# Grove_-_Barometer_Sensor_BMP280_v1_0.net
KiCad netlist of a schematic drawn in EAGLE
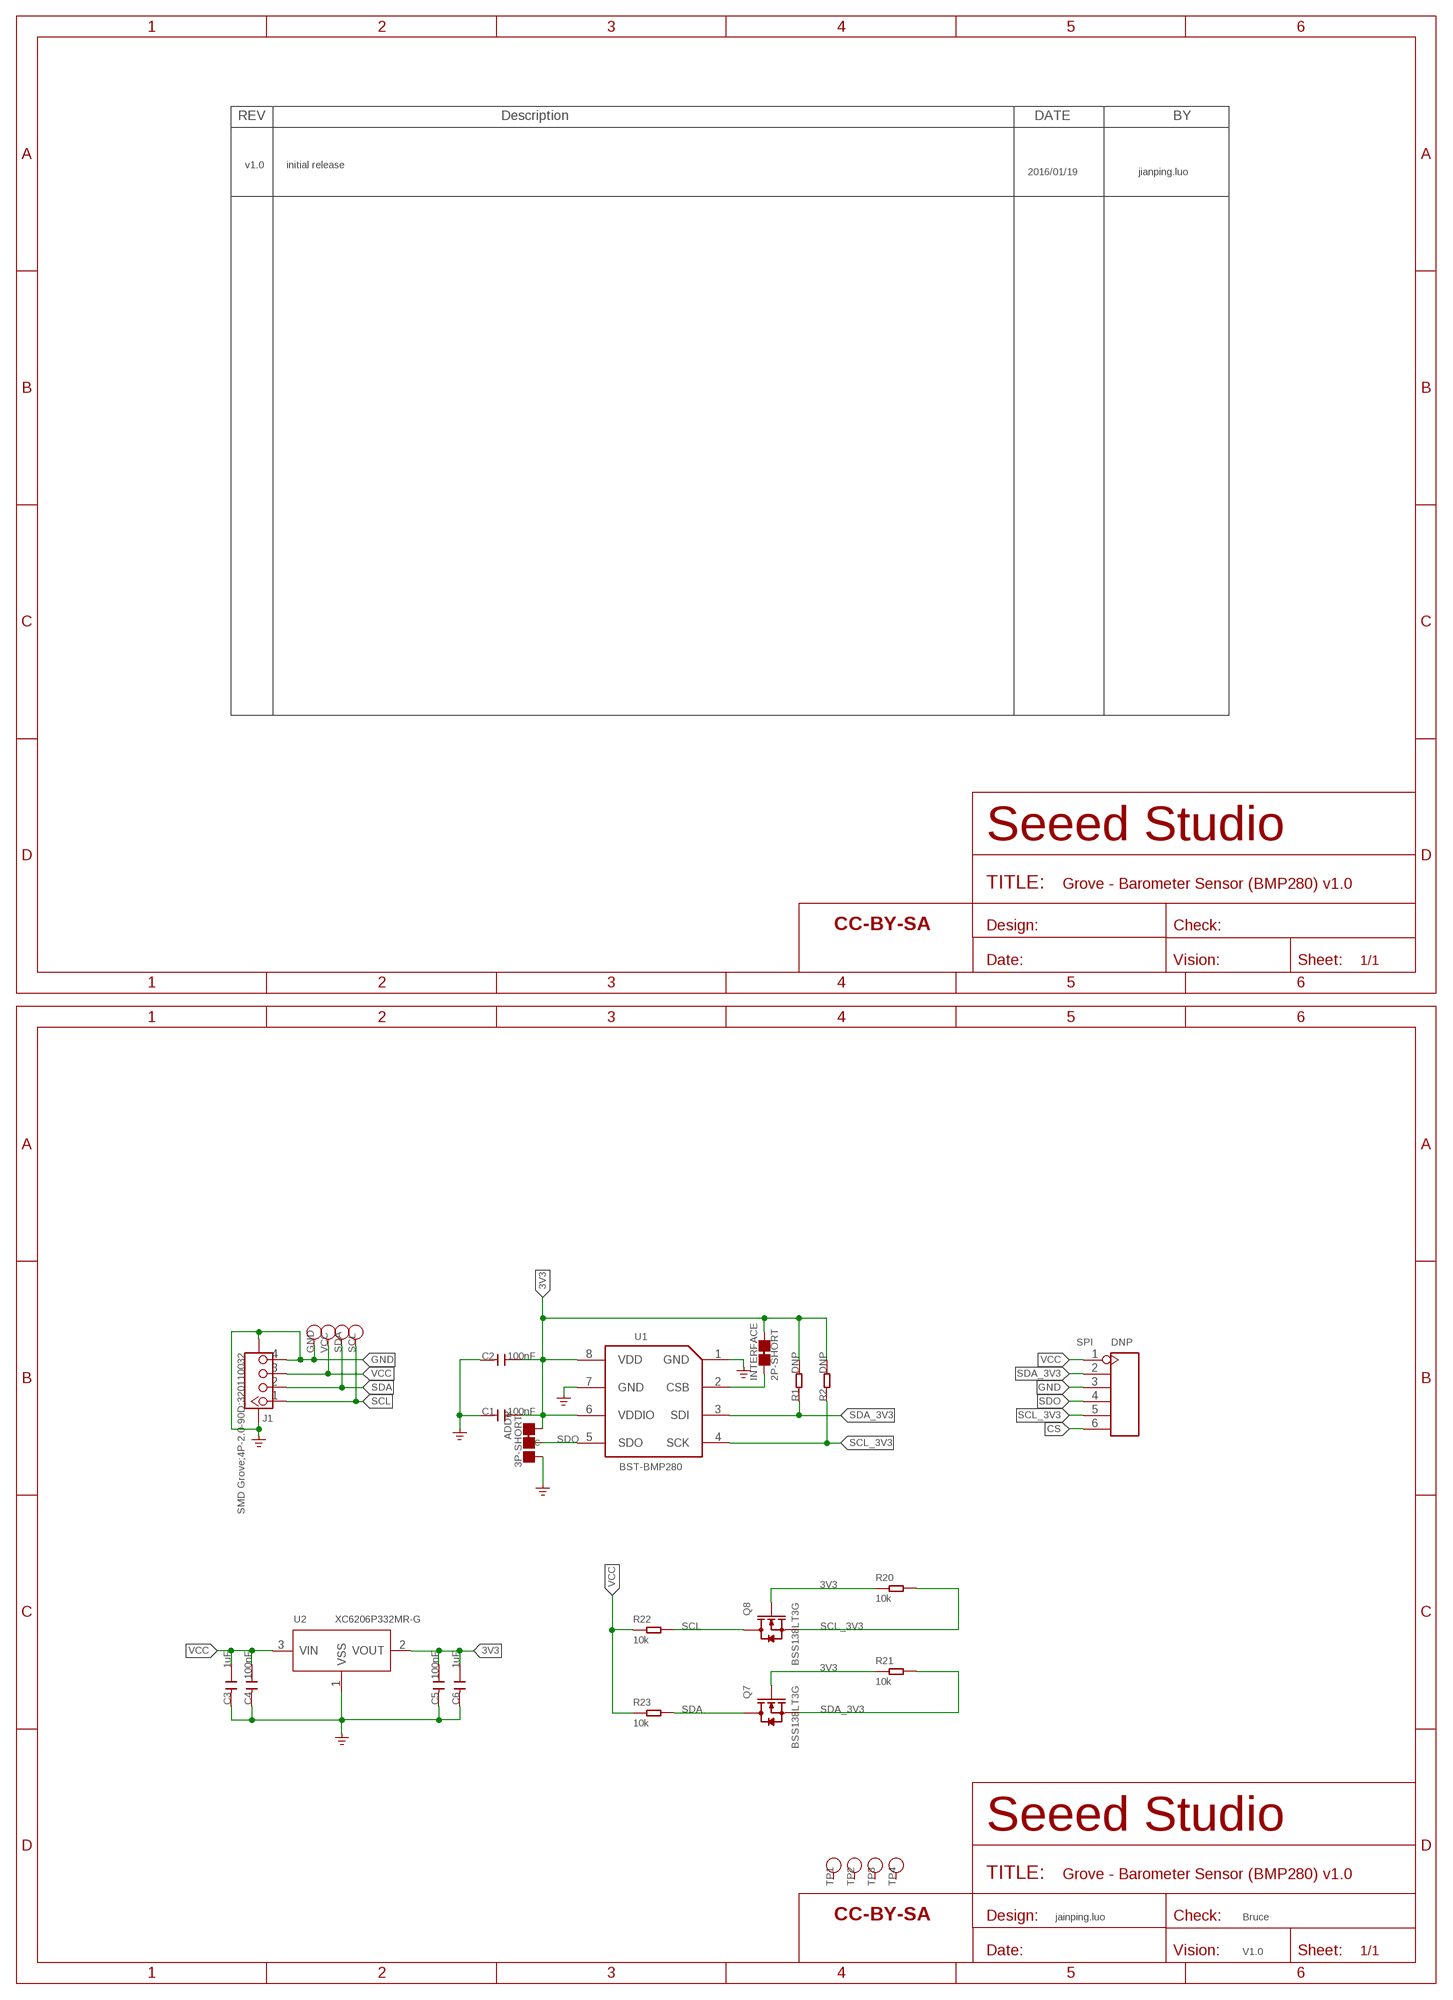
[diagram p0: schematic, sheet 1]

(export (version "E")
  (design (tool "Eeschema 10.0.6"))
  (components
    (comp (ref "ADDR")
      (value "3P-SHORT")
      (footprint "eagle-import:3P-SMD-SHORT")
      (libsource (lib "eagle-import") (part "JUMPER-3P-SHORT"))
    )
    (comp (ref "C1")
      (value "100nF")
      (footprint "eagle-import:C0603")
      (libsource (lib "eagle-import") (part "CAP-0603"))
    )
    (comp (ref "C2")
      (value "100nF")
      (footprint "eagle-import:C0603")
      (libsource (lib "eagle-import") (part "CAP-0603"))
    )
    (comp (ref "C3")
      (value "1uF")
      (footprint "eagle-import:C0603")
      (libsource (lib "eagle-import") (part "CAP-0603"))
    )
    (comp (ref "C4")
      (value "100nF")
      (footprint "eagle-import:C0603")
      (libsource (lib "eagle-import") (part "CAP-0603"))
    )
    (comp (ref "C5")
      (value "100nF")
      (footprint "eagle-import:C0603")
      (libsource (lib "eagle-import") (part "CAP-0603"))
    )
    (comp (ref "C6")
      (value "1uF")
      (footprint "eagle-import:C0603")
      (libsource (lib "eagle-import") (part "CAP-0603"))
    )
    (comp (ref "FR1")
      (value "SEEEDSTUDIO-OPEN-SCH-FRAME")
      (footprint "eagle-import:SEEEDSTUDIO-PCB-FRAME")
      (libsource (lib "eagle-import") (part "SEEEDSTUDIO-OPEN-SCH-FRAME"))
    )
    (comp (ref "FR2")
      (value "SEEEDSTUDIO-OPEN-SCH-FRAME")
      (footprint "eagle-import:SEEEDSTUDIO-PCB-FRAME")
      (libsource (lib "eagle-import") (part "SEEEDSTUDIO-OPEN-SCH-FRAME"))
    )
    (comp (ref "GND")
      (value "TEST-POINT'4545'")
      (footprint "eagle-import:TP-D45MIL")
      (fields (field (name "PARTNO") "DNP"))
      (libsource (lib "eagle-import") (part "TEST-POINT'4545'"))
    )
    (comp (ref "INTERFACE")
      (value "2P-SHORT")
      (footprint "eagle-import:2P-SMD-SHORT")
      (libsource (lib "eagle-import") (part "JUMPER-2P-SHORT"))
    )
    (comp (ref "J1")
      (value "SMD Grove;4P-2.0-90D;320110032")
      (footprint "eagle-import:HW4-SMD-2.0-90D")
      (libsource (lib "eagle-import") (part "GROVE-CONNECTOR-SMD'90D'"))
    )
    (comp (ref "Q7")
      (value "BSS138LT3G")
      (footprint "eagle-import:SOT-23")
      (libsource (lib "eagle-import") (part "MOSFET-N'SOT23'"))
    )
    (comp (ref "Q8")
      (value "BSS138LT3G")
      (footprint "eagle-import:SOT-23")
      (libsource (lib "eagle-import") (part "MOSFET-N'SOT23'"))
    )
    (comp (ref "R1")
      (value "DNP")
      (footprint "eagle-import:R0603")
      (libsource (lib "eagle-import") (part "RES-0603"))
    )
    (comp (ref "R2")
      (value "DNP")
      (footprint "eagle-import:R0603")
      (libsource (lib "eagle-import") (part "RES-0603"))
    )
    (comp (ref "R20")
      (value "10k")
      (footprint "eagle-import:R0603")
      (libsource (lib "eagle-import") (part "RES-0603"))
    )
    (comp (ref "R21")
      (value "10k")
      (footprint "eagle-import:R0603")
      (libsource (lib "eagle-import") (part "RES-0603"))
    )
    (comp (ref "R22")
      (value "10k")
      (footprint "eagle-import:R0603")
      (libsource (lib "eagle-import") (part "RES-0603"))
    )
    (comp (ref "R23")
      (value "10k")
      (footprint "eagle-import:R0603")
      (libsource (lib "eagle-import") (part "RES-0603"))
    )
    (comp (ref "SCL")
      (value "TEST-POINT'4545'")
      (footprint "eagle-import:TP-D45MIL")
      (fields (field (name "PARTNO") "DNP"))
      (libsource (lib "eagle-import") (part "TEST-POINT'4545'"))
    )
    (comp (ref "SDA")
      (value "TEST-POINT'4545'")
      (footprint "eagle-import:TP-D45MIL")
      (fields (field (name "PARTNO") "DNP"))
      (libsource (lib "eagle-import") (part "TEST-POINT'4545'"))
    )
    (comp (ref "SPI")
      (value "DNP")
      (footprint "eagle-import:H6-2.54-C65D35MIL")
      (libsource (lib "eagle-import") (part "HEADER-6P-65/35MIL"))
    )
    (comp (ref "TP1")
      (value "TEST-POINT'4545'")
      (footprint "eagle-import:TP-D45MIL")
      (fields (field (name "PARTNO") "DNP"))
      (libsource (lib "eagle-import") (part "TEST-POINT'4545'"))
    )
    (comp (ref "TP2")
      (value "TEST-POINT'4545'")
      (footprint "eagle-import:TP-D45MIL")
      (fields (field (name "PARTNO") "DNP"))
      (libsource (lib "eagle-import") (part "TEST-POINT'4545'"))
    )
    (comp (ref "TP3")
      (value "TEST-POINT'4545'")
      (footprint "eagle-import:TP-D45MIL")
      (fields (field (name "PARTNO") "DNP"))
      (libsource (lib "eagle-import") (part "TEST-POINT'4545'"))
    )
    (comp (ref "TP4")
      (value "TEST-POINT'4545'")
      (footprint "eagle-import:TP-D45MIL")
      (fields (field (name "PARTNO") "DNP"))
      (libsource (lib "eagle-import") (part "TEST-POINT'4545'"))
    )
    (comp (ref "U1")
      (value "BST-BMP280")
      (footprint "eagle-import:LGA8-0.65-2X2.5X0.95MM")
      (fields (field (name "MPN") "BMP280"))
      (libsource (lib "eagle-import") (part "SENSOR-BMP280"))
    )
    (comp (ref "U2")
      (value "XC6206P332MR-G")
      (footprint "eagle-import:SOT-23")
      (libsource (lib "eagle-import") (part "PMIC-XC6206PMR"))
    )
    (comp (ref "VCC")
      (value "TEST-POINT'4545'")
      (footprint "eagle-import:TP-D45MIL")
      (fields (field (name "PARTNO") "DNP"))
      (libsource (lib "eagle-import") (part "TEST-POINT'4545'"))
    )
  )
  (nets
    (net (code "1") (name "3V3") (class "Default")
      (node (ref "ADDR") (pin "11") (pinfunction "L_11") (pintype "bidirectional"))
      (node (ref "C1") (pin "1") (pinfunction "1_1") (pintype "passive"))
      (node (ref "C2") (pin "1") (pinfunction "1_1") (pintype "passive"))
      (node (ref "C5") (pin "1") (pinfunction "1_1") (pintype "passive"))
      (node (ref "C6") (pin "1") (pinfunction "1_1") (pintype "passive"))
      (node (ref "INTERFACE") (pin "2") (pinfunction "2_2") (pintype "bidirectional"))
      (node (ref "Q7") (pin "1") (pinfunction "G_1") (pintype "passive"))
      (node (ref "Q8") (pin "1") (pinfunction "G_1") (pintype "passive"))
      (node (ref "R1") (pin "2") (pinfunction "2_2") (pintype "passive"))
      (node (ref "R2") (pin "2") (pinfunction "2_2") (pintype "passive"))
      (node (ref "R20") (pin "1") (pinfunction "1_1") (pintype "passive"))
      (node (ref "R21") (pin "1") (pinfunction "1_1") (pintype "passive"))
      (node (ref "U1") (pin "6") (pinfunction "VDDIO_6") (pintype "power_in"))
      (node (ref "U1") (pin "8") (pinfunction "VDD_8") (pintype "power_in"))
      (node (ref "U2") (pin "2") (pinfunction "VOUT_2") (pintype "bidirectional"))
    )
    (net (code "2") (name "CS") (class "Default")
      (node (ref "INTERFACE") (pin "1") (pinfunction "1_1") (pintype "bidirectional"))
      (node (ref "SPI") (pin "6") (pinfunction "6_6") (pintype "bidirectional"))
      (node (ref "U1") (pin "2") (pinfunction "CSB_2") (pintype "bidirectional"))
    )
    (net (code "3") (name "GND") (class "Default")
      (node (ref "ADDR") (pin "00") (pinfunction "R_00") (pintype "bidirectional"))
      (node (ref "C1") (pin "2") (pinfunction "2_2") (pintype "passive"))
      (node (ref "C2") (pin "2") (pinfunction "2_2") (pintype "passive"))
      (node (ref "C3") (pin "2") (pinfunction "2_2") (pintype "passive"))
      (node (ref "C4") (pin "2") (pinfunction "2_2") (pintype "passive"))
      (node (ref "C5") (pin "2") (pinfunction "2_2") (pintype "passive"))
      (node (ref "C6") (pin "2") (pinfunction "2_2") (pintype "passive"))
      (node (ref "GND") (pin "T") (pinfunction "T_T") (pintype "bidirectional"))
      (node (ref "J1") (pin "4") (pinfunction "4_4") (pintype "bidirectional"))
      (node (ref "J1") (pin "SS1") (pinfunction "SS1_SS1") (pintype "bidirectional"))
      (node (ref "J1") (pin "SS2") (pinfunction "SS2_SS2") (pintype "bidirectional"))
      (node (ref "SPI") (pin "3") (pinfunction "3_3") (pintype "bidirectional"))
      (node (ref "U1") (pin "1") (pinfunction "GND_1") (pintype "power_in"))
      (node (ref "U1") (pin "7") (pinfunction "GND_7") (pintype "power_in"))
      (node (ref "U2") (pin "1") (pinfunction "VSS_1") (pintype "bidirectional"))
    )
    (net (code "4") (name "SCL") (class "Default")
      (node (ref "J1") (pin "1") (pinfunction "1_1") (pintype "bidirectional"))
      (node (ref "Q8") (pin "3") (pinfunction "D_3") (pintype "passive"))
      (node (ref "R22") (pin "2") (pinfunction "2_2") (pintype "passive"))
      (node (ref "SCL") (pin "T") (pinfunction "T_T") (pintype "bidirectional"))
    )
    (net (code "5") (name "SCL_3V3") (class "Default")
      (node (ref "Q8") (pin "2") (pinfunction "S_2") (pintype "passive"))
      (node (ref "R2") (pin "1") (pinfunction "1_1") (pintype "passive"))
      (node (ref "R20") (pin "2") (pinfunction "2_2") (pintype "passive"))
      (node (ref "SPI") (pin "5") (pinfunction "5_5") (pintype "bidirectional"))
      (node (ref "U1") (pin "4") (pinfunction "SCK_4") (pintype "bidirectional"))
    )
    (net (code "6") (name "SDA") (class "Default")
      (node (ref "J1") (pin "2") (pinfunction "2_2") (pintype "bidirectional"))
      (node (ref "Q7") (pin "3") (pinfunction "D_3") (pintype "passive"))
      (node (ref "R23") (pin "2") (pinfunction "2_2") (pintype "passive"))
      (node (ref "SDA") (pin "T") (pinfunction "T_T") (pintype "bidirectional"))
    )
    (net (code "7") (name "SDA_3V3") (class "Default")
      (node (ref "Q7") (pin "2") (pinfunction "S_2") (pintype "passive"))
      (node (ref "R1") (pin "1") (pinfunction "1_1") (pintype "passive"))
      (node (ref "R21") (pin "2") (pinfunction "2_2") (pintype "passive"))
      (node (ref "SPI") (pin "2") (pinfunction "2_2") (pintype "bidirectional"))
      (node (ref "U1") (pin "3") (pinfunction "SDI_3") (pintype "bidirectional"))
    )
    (net (code "8") (name "SDO") (class "Default")
      (node (ref "ADDR") (pin "MM") (pinfunction "C_MM") (pintype "bidirectional"))
      (node (ref "SPI") (pin "4") (pinfunction "4_4") (pintype "bidirectional"))
      (node (ref "U1") (pin "5") (pinfunction "SDO_5") (pintype "bidirectional"))
    )
    (net (code "9") (name "VCC") (class "Default")
      (node (ref "C3") (pin "1") (pinfunction "1_1") (pintype "passive"))
      (node (ref "C4") (pin "1") (pinfunction "1_1") (pintype "passive"))
      (node (ref "J1") (pin "3") (pinfunction "3_3") (pintype "bidirectional"))
      (node (ref "R22") (pin "1") (pinfunction "1_1") (pintype "passive"))
      (node (ref "R23") (pin "1") (pinfunction "1_1") (pintype "passive"))
      (node (ref "SPI") (pin "1") (pinfunction "1_1") (pintype "bidirectional"))
      (node (ref "U2") (pin "3") (pinfunction "VIN_3") (pintype "bidirectional"))
      (node (ref "VCC") (pin "T") (pinfunction "T_T") (pintype "bidirectional"))
    )
    (net (code "10") (name "unconnected-(TP1-PadT)") (class "Default")
      (node (ref "TP1") (pin "T") (pinfunction "T_T") (pintype "bidirectional"))
    )
    (net (code "11") (name "unconnected-(TP2-PadT)") (class "Default")
      (node (ref "TP2") (pin "T") (pinfunction "T_T") (pintype "bidirectional"))
    )
    (net (code "12") (name "unconnected-(TP3-PadT)") (class "Default")
      (node (ref "TP3") (pin "T") (pinfunction "T_T") (pintype "bidirectional"))
    )
    (net (code "13") (name "unconnected-(TP4-PadT)") (class "Default")
      (node (ref "TP4") (pin "T") (pinfunction "T_T") (pintype "bidirectional"))
    )
  )
)
